# 5v_3v3_500ma.net
KiCad netlist of a schematic drawn in EAGLE
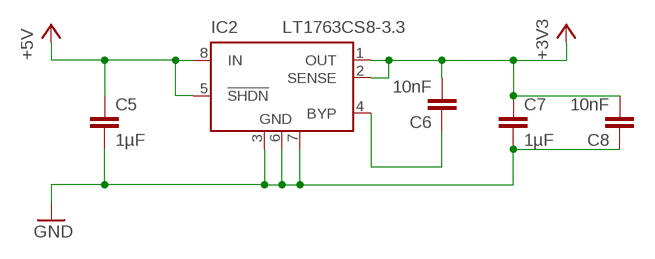
[diagram p0: schematic, sheet 1]

(export (version "E")
  (design (tool "Eeschema 10.0.6"))
  (components
    (comp (ref "C5")
      (value "1µF")
      (footprint "eagle-import:0805")
      (libsource (lib "eagle-import") (part "CAP0805"))
    )
    (comp (ref "C6")
      (value "10nF")
      (footprint "eagle-import:C0402")
      (libsource (lib "eagle-import") (part "C-EUC0402"))
    )
    (comp (ref "C7")
      (value "1µF")
      (footprint "eagle-import:0805")
      (libsource (lib "eagle-import") (part "CAP0805"))
    )
    (comp (ref "C8")
      (value "10nF")
      (footprint "eagle-import:C0402")
      (libsource (lib "eagle-import") (part "C-EUC0402"))
    )
    (comp (ref "IC2")
      (value "LT1763CS8-3.3")
      (footprint "eagle-import:SOIC8")
      (libsource (lib "eagle-import") (part "LT1763CS8-3.3"))
    )
  )
  (nets
    (net (code "1") (name "+3V3") (class "Default")
      (node (ref "C6") (pin "2") (pinfunction "2_2") (pintype "passive"))
      (node (ref "C7") (pin "1") (pinfunction "1_1") (pintype "passive"))
      (node (ref "C8") (pin "2") (pinfunction "2_2") (pintype "passive"))
      (node (ref "IC2") (pin "1") (pinfunction "OUT_1") (pintype "passive"))
      (node (ref "IC2") (pin "2") (pinfunction "SENSE_2") (pintype "input"))
    )
    (net (code "2") (name "+5V") (class "Default")
      (node (ref "C5") (pin "1") (pinfunction "1_1") (pintype "passive"))
      (node (ref "IC2") (pin "5") (pinfunction "~{SHDN}_5") (pintype "input"))
      (node (ref "IC2") (pin "8") (pinfunction "IN_8") (pintype "input"))
    )
    (net (code "3") (name "GND") (class "Default")
      (node (ref "C5") (pin "2") (pinfunction "2_2") (pintype "passive"))
      (node (ref "C7") (pin "2") (pinfunction "2_2") (pintype "passive"))
      (node (ref "C8") (pin "1") (pinfunction "1_1") (pintype "passive"))
      (node (ref "IC2") (pin "3") (pinfunction "GND_3") (pintype "power_in"))
      (node (ref "IC2") (pin "6") (pinfunction "GND_6") (pintype "power_in"))
      (node (ref "IC2") (pin "7") (pinfunction "GND_7") (pintype "power_in"))
    )
    (net (code "4") (name "Net-(IC2-BYP)") (class "Default")
      (node (ref "C6") (pin "1") (pinfunction "1_1") (pintype "passive"))
      (node (ref "IC2") (pin "4") (pinfunction "BYP_4") (pintype "input"))
    )
  )
)
